# watch_game_2022_revB.net
KiCad netlist of a schematic drawn in EAGLE
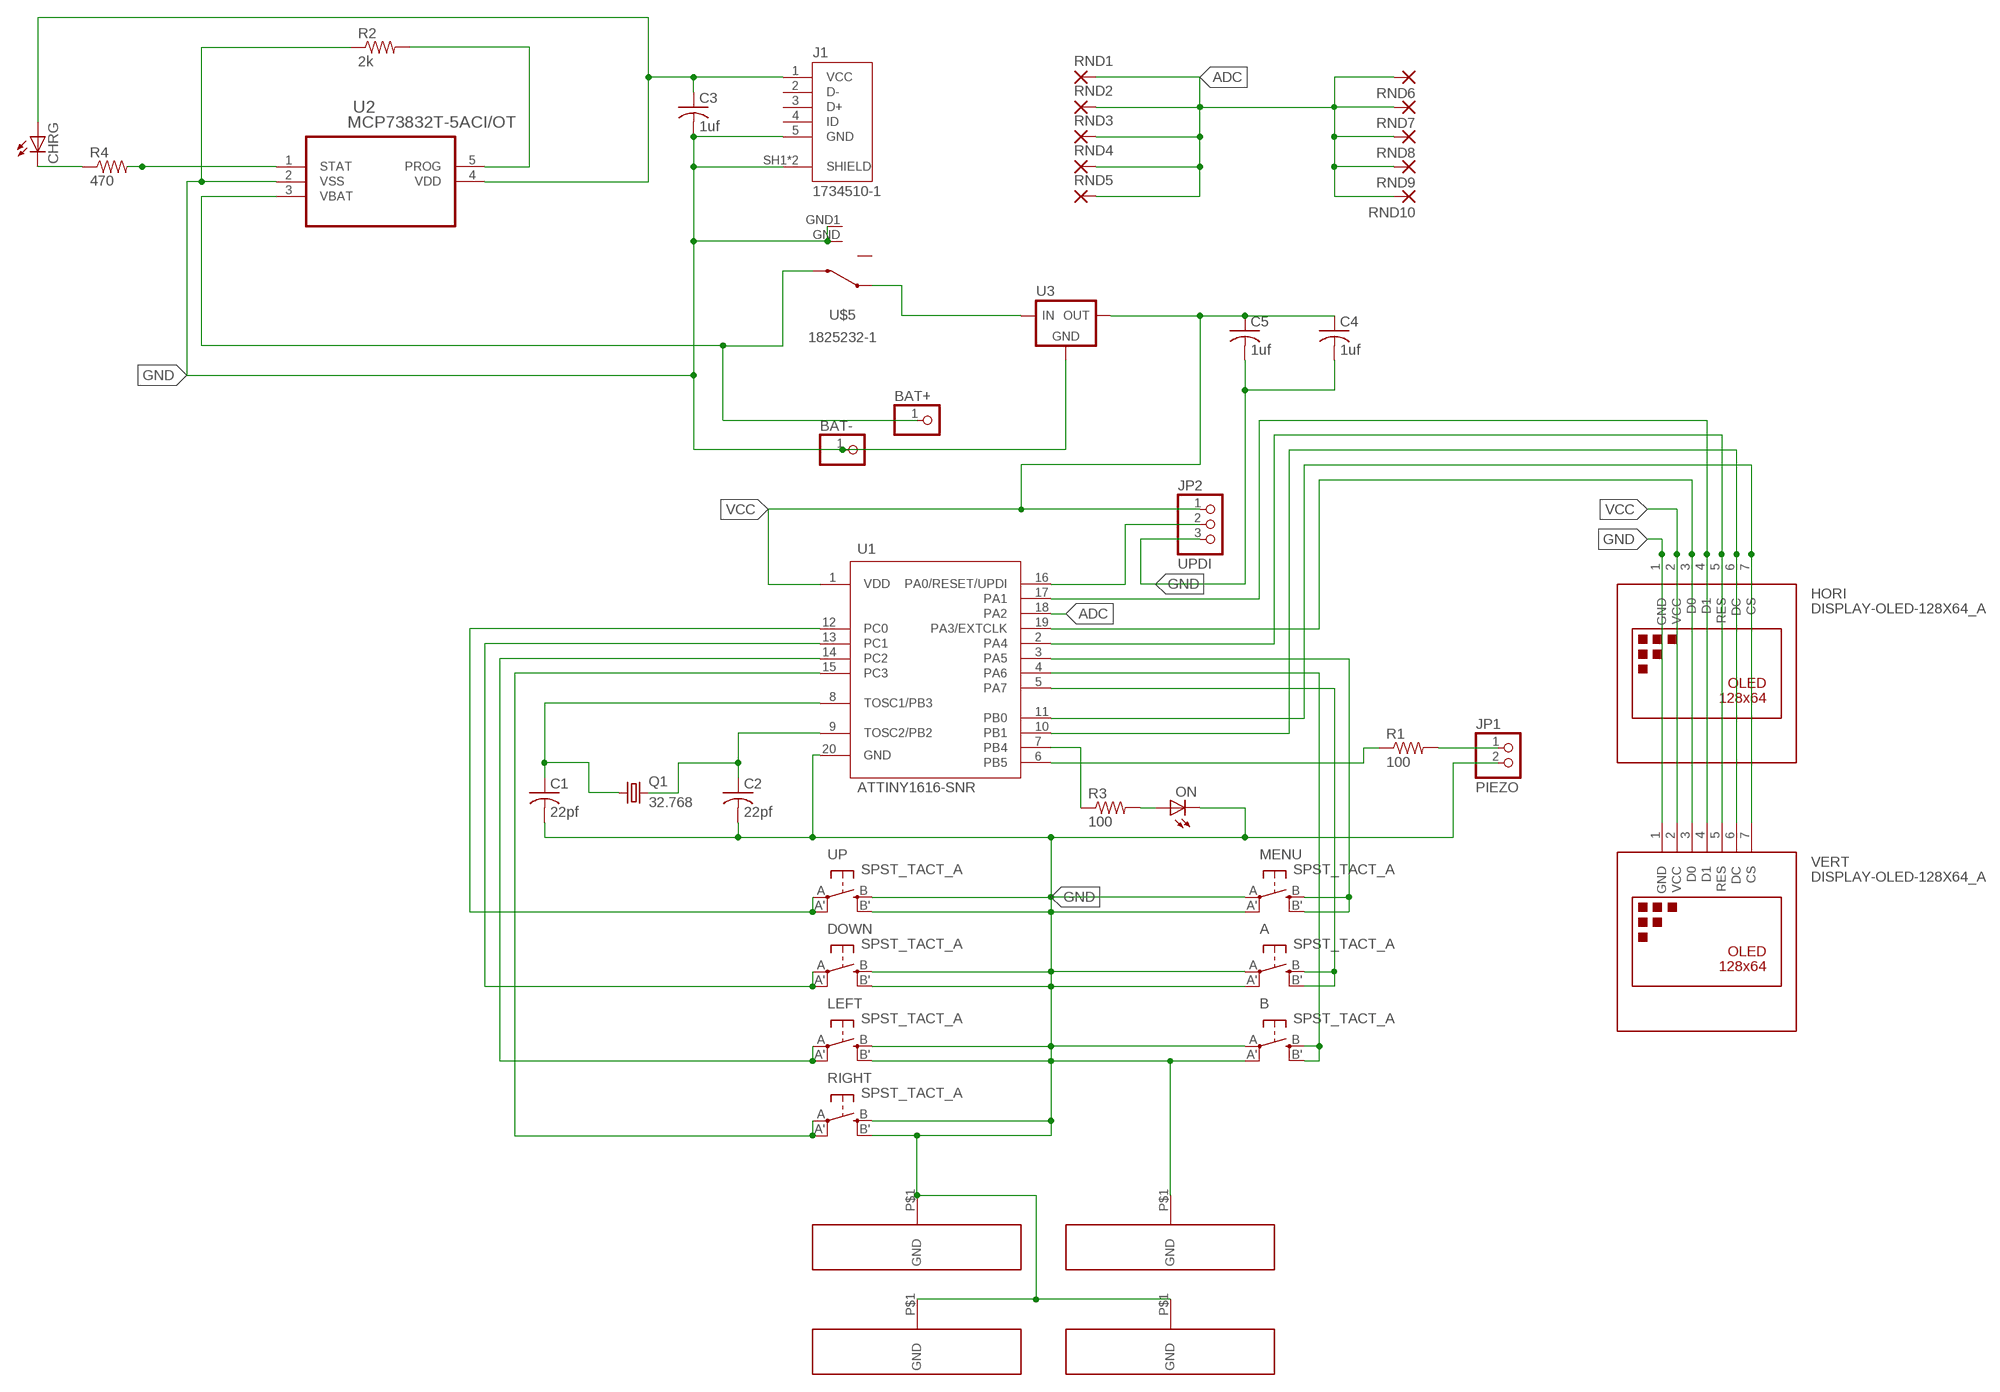
[diagram p0: schematic, sheet 1]

(export (version "E")
  (design (tool "Eeschema 10.0.6"))
  (components
    (comp (ref "A")
      (value "SPST_TACT_A")
      (footprint "eagle-import:EVQ-Q2_A")
      (libsource (lib "eagle-import") (part "SPST_TACT_A"))
    )
    (comp (ref "B")
      (value "SPST_TACT_A")
      (footprint "eagle-import:EVQ-Q2_A")
      (libsource (lib "eagle-import") (part "SPST_TACT_A"))
    )
    (comp (ref "BAT+")
      (value "PINHD-1X1")
      (footprint "eagle-import:1X01")
      (libsource (lib "eagle-import") (part "PINHD-1X1"))
    )
    (comp (ref "BAT-")
      (value "PINHD-1X1")
      (footprint "eagle-import:1X01")
      (libsource (lib "eagle-import") (part "PINHD-1X1"))
    )
    (comp (ref "C1")
      (value "22pf")
      (footprint "eagle-import:C0805")
      (libsource (lib "eagle-import") (part "C-USC0805"))
    )
    (comp (ref "C2")
      (value "22pf")
      (footprint "eagle-import:C0805")
      (libsource (lib "eagle-import") (part "C-USC0805"))
    )
    (comp (ref "C3")
      (value "1uf")
      (footprint "eagle-import:C0805")
      (libsource (lib "eagle-import") (part "rcl_334_C-USC0805"))
    )
    (comp (ref "C4")
      (value "1uf")
      (footprint "eagle-import:C0805")
      (libsource (lib "eagle-import") (part "rcl_334_C-USC0805"))
    )
    (comp (ref "C5")
      (value "1uf")
      (footprint "eagle-import:C0805")
      (libsource (lib "eagle-import") (part "rcl_334_C-USC0805"))
    )
    (comp (ref "CHRG")
      (value "LED3MM")
      (footprint "eagle-import:LED3MM")
      (libsource (lib "eagle-import") (part "LED3MM"))
    )
    (comp (ref "DOWN")
      (value "SPST_TACT_A")
      (footprint "eagle-import:EVQ-Q2_A")
      (libsource (lib "eagle-import") (part "SPST_TACT_A"))
    )
    (comp (ref "HORI")
      (value "DISPLAY-OLED-128X64_A")
      (footprint "eagle-import:DISPLAY-OLED-128X64_A")
      (libsource (lib "eagle-import") (part "DISPLAY-OLED-128X64_A"))
    )
    (comp (ref "J1")
      (value "1734510-1")
      (footprint "eagle-import:TE_1734510-1")
      (fields (field (name "MF") "TE Connectivity"))
      (libsource (lib "eagle-import") (part "1734510-1"))
    )
    (comp (ref "JP1")
      (value "PIEZO")
      (footprint "eagle-import:1X02")
      (libsource (lib "eagle-import") (part "PINHD-1X2"))
    )
    (comp (ref "JP2")
      (value "UPDI")
      (footprint "eagle-import:1X03")
      (libsource (lib "eagle-import") (part "PINHD-1X3"))
    )
    (comp (ref "LEFT")
      (value "SPST_TACT_A")
      (footprint "eagle-import:EVQ-Q2_A")
      (libsource (lib "eagle-import") (part "SPST_TACT_A"))
    )
    (comp (ref "MENU")
      (value "SPST_TACT_A")
      (footprint "eagle-import:EVQ-Q2_A")
      (libsource (lib "eagle-import") (part "SPST_TACT_A"))
    )
    (comp (ref "ON")
      (value "LED5MM")
      (footprint "eagle-import:LED5MM")
      (libsource (lib "eagle-import") (part "led_259_LED5MM"))
    )
    (comp (ref "Q1")
      (value "32.768")
      (footprint "eagle-import:TC26H")
      (libsource (lib "eagle-import") (part "CRYSTALTC26H"))
    )
    (comp (ref "R1")
      (value "100")
      (footprint "eagle-import:M0805")
      (libsource (lib "eagle-import") (part "R-US_M0805"))
    )
    (comp (ref "R2")
      (value "2k")
      (footprint "eagle-import:M0805")
      (libsource (lib "eagle-import") (part "R-US_M0805"))
    )
    (comp (ref "R3")
      (value "100")
      (footprint "eagle-import:M0805")
      (libsource (lib "eagle-import") (part "R-US_M0805"))
    )
    (comp (ref "R4")
      (value "470")
      (footprint "eagle-import:M0805")
      (libsource (lib "eagle-import") (part "R-US_M0805"))
    )
    (comp (ref "RIGHT")
      (value "SPST_TACT_A")
      (footprint "eagle-import:EVQ-Q2_A")
      (libsource (lib "eagle-import") (part "SPST_TACT_A"))
    )
    (comp (ref "RND1")
      (value "SMD5")
      (footprint "eagle-import:SMD2,54-5,08")
      (libsource (lib "eagle-import") (part "SMD5"))
    )
    (comp (ref "RND2")
      (value "SMD5")
      (footprint "eagle-import:SMD2,54-5,08")
      (libsource (lib "eagle-import") (part "SMD5"))
    )
    (comp (ref "RND3")
      (value "SMD5")
      (footprint "eagle-import:SMD2,54-5,08")
      (libsource (lib "eagle-import") (part "SMD5"))
    )
    (comp (ref "RND4")
      (value "SMD5")
      (footprint "eagle-import:SMD2,54-5,08")
      (libsource (lib "eagle-import") (part "SMD5"))
    )
    (comp (ref "RND5")
      (value "SMD5")
      (footprint "eagle-import:SMD2,54-5,08")
      (libsource (lib "eagle-import") (part "SMD5"))
    )
    (comp (ref "RND6")
      (value "SMD5")
      (footprint "eagle-import:SMD2,54-5,08")
      (libsource (lib "eagle-import") (part "SMD5"))
    )
    (comp (ref "RND7")
      (value "SMD5")
      (footprint "eagle-import:SMD2,54-5,08")
      (libsource (lib "eagle-import") (part "SMD5"))
    )
    (comp (ref "RND8")
      (value "SMD5")
      (footprint "eagle-import:SMD2,54-5,08")
      (libsource (lib "eagle-import") (part "SMD5"))
    )
    (comp (ref "RND9")
      (value "SMD5")
      (footprint "eagle-import:SMD2,54-5,08")
      (libsource (lib "eagle-import") (part "SMD5"))
    )
    (comp (ref "RND10")
      (value "SMD5")
      (footprint "eagle-import:SMD2,54-5,08")
      (libsource (lib "eagle-import") (part "SMD5"))
    )
    (comp (ref "U$5")
      (value "1825232-1")
      (footprint "eagle-import:1825232-1")
      (fields (field (name "MF") "TE Connectivity"))
      (libsource (lib "eagle-import") (part "1825232-1"))
    )
    (comp (ref "U$6")
      (value "GND_STRIP_600MIL")
      (footprint "eagle-import:GND_PADS_2")
      (libsource (lib "eagle-import") (part "GND_STRIP_600MIL"))
    )
    (comp (ref "U$7")
      (value "GND_STRIP_600MIL")
      (footprint "eagle-import:GND_PADS_2")
      (libsource (lib "eagle-import") (part "GND_STRIP_600MIL"))
    )
    (comp (ref "U$8")
      (value "GND_STRIP_600MIL")
      (footprint "eagle-import:GND_PADS_2")
      (libsource (lib "eagle-import") (part "GND_STRIP_600MIL"))
    )
    (comp (ref "U$9")
      (value "GND_STRIP_600MIL")
      (footprint "eagle-import:GND_PADS_2")
      (libsource (lib "eagle-import") (part "GND_STRIP_600MIL"))
    )
    (comp (ref "U1")
      (value "ATTINY1616-SNR")
      (footprint "eagle-import:SOIC127P1032X265-20N")
      (fields (field (name "MF") "Microchip"))
      (libsource (lib "eagle-import") (part "ATTINY1616-SNR"))
    )
    (comp (ref "U2")
      (value "MCP73832T-5ACI/OT")
      (footprint "eagle-import:SOT95P300X145-5N")
      (fields (field (name "MF") "Microchip"))
      (libsource (lib "eagle-import") (part "MCP73832T-5ACI/OT"))
    )
    (comp (ref "U3")
      (value "NCP5501DT33RKG")
      (footprint "eagle-import:DPAK")
      (libsource (lib "eagle-import") (part "NCP5501DT33RKG"))
    )
    (comp (ref "UP")
      (value "SPST_TACT_A")
      (footprint "eagle-import:EVQ-Q2_A")
      (libsource (lib "eagle-import") (part "SPST_TACT_A"))
    )
    (comp (ref "VERT")
      (value "DISPLAY-OLED-128X64_A")
      (footprint "eagle-import:DISPLAY-OLED-128X64_A")
      (libsource (lib "eagle-import") (part "DISPLAY-OLED-128X64_A"))
    )
  )
  (nets
    (net (code "1") (name "ADC") (class "Default")
      (node (ref "RND1") (pin "1") (pinfunction "P_1") (pintype "passive"))
      (node (ref "RND10") (pin "1") (pinfunction "P_1") (pintype "passive"))
      (node (ref "RND2") (pin "1") (pinfunction "P_1") (pintype "passive"))
      (node (ref "RND3") (pin "1") (pinfunction "P_1") (pintype "passive"))
      (node (ref "RND4") (pin "1") (pinfunction "P_1") (pintype "passive"))
      (node (ref "RND5") (pin "1") (pinfunction "P_1") (pintype "passive"))
      (node (ref "RND6") (pin "1") (pinfunction "P_1") (pintype "passive"))
      (node (ref "RND7") (pin "1") (pinfunction "P_1") (pintype "passive"))
      (node (ref "RND8") (pin "1") (pinfunction "P_1") (pintype "passive"))
      (node (ref "RND9") (pin "1") (pinfunction "P_1") (pintype "passive"))
      (node (ref "U1") (pin "18") (pinfunction "PA2_18") (pintype "bidirectional"))
    )
    (net (code "2") (name "GND") (class "Default")
      (node (ref "A") (pin "A") (pinfunction "P_A") (pintype "passive"))
      (node (ref "A") (pin "A'") (pinfunction "P1_A'") (pintype "passive"))
      (node (ref "B") (pin "A") (pinfunction "P_A") (pintype "passive"))
      (node (ref "B") (pin "A'") (pinfunction "P1_A'") (pintype "passive"))
      (node (ref "BAT-") (pin "1") (pinfunction "1_1") (pintype "passive"))
      (node (ref "C1") (pin "2") (pinfunction "2_2") (pintype "passive"))
      (node (ref "C2") (pin "2") (pinfunction "2_2") (pintype "passive"))
      (node (ref "C3") (pin "2") (pinfunction "2_2") (pintype "passive"))
      (node (ref "C4") (pin "2") (pinfunction "2_2") (pintype "passive"))
      (node (ref "C5") (pin "2") (pinfunction "2_2") (pintype "passive"))
      (node (ref "DOWN") (pin "B") (pinfunction "S_B") (pintype "passive"))
      (node (ref "DOWN") (pin "B'") (pinfunction "S1_B'") (pintype "passive"))
      (node (ref "HORI") (pin "1") (pinfunction "GND_1") (pintype "power_in"))
      (node (ref "J1") (pin "5") (pinfunction "GND_5") (pintype "passive"))
      (node (ref "J1") (pin "SH1") (pinfunction "SHIELD_SH1") (pintype "passive"))
      (node (ref "J1") (pin "SH2") (pinfunction "SHIELD_SH2") (pintype "passive"))
      (node (ref "JP1") (pin "2") (pinfunction "2_2") (pintype "passive"))
      (node (ref "JP2") (pin "3") (pinfunction "3_3") (pintype "passive"))
      (node (ref "LEFT") (pin "B") (pinfunction "S_B") (pintype "passive"))
      (node (ref "LEFT") (pin "B'") (pinfunction "S1_B'") (pintype "passive"))
      (node (ref "MENU") (pin "A") (pinfunction "P_A") (pintype "passive"))
      (node (ref "MENU") (pin "A'") (pinfunction "P1_A'") (pintype "passive"))
      (node (ref "ON") (pin "K") (pinfunction "C_K") (pintype "passive"))
      (node (ref "R2") (pin "1") (pinfunction "1_1") (pintype "passive"))
      (node (ref "RIGHT") (pin "B") (pinfunction "S_B") (pintype "passive"))
      (node (ref "RIGHT") (pin "B'") (pinfunction "S1_B'") (pintype "passive"))
      (node (ref "U$5") (pin "GND") (pinfunction "GND_GND") (pintype "passive"))
      (node (ref "U$5") (pin "GND1") (pinfunction "GND1_GND1") (pintype "passive"))
      (node (ref "U$6") (pin "P$1") (pinfunction "GND_P$1") (pintype "bidirectional"))
      (node (ref "U$7") (pin "P$1") (pinfunction "GND_P$1") (pintype "bidirectional"))
      (node (ref "U$8") (pin "P$1") (pinfunction "GND_P$1") (pintype "bidirectional"))
      (node (ref "U$9") (pin "P$1") (pinfunction "GND_P$1") (pintype "bidirectional"))
      (node (ref "U1") (pin "20") (pinfunction "GND_20") (pintype "power_in"))
      (node (ref "U2") (pin "2") (pinfunction "VSS_2") (pintype "passive"))
      (node (ref "U3") (pin "4") (pinfunction "GND_4") (pintype "power_in"))
      (node (ref "UP") (pin "B") (pinfunction "S_B") (pintype "passive"))
      (node (ref "UP") (pin "B'") (pinfunction "S1_B'") (pintype "passive"))
      (node (ref "VERT") (pin "1") (pinfunction "GND_1") (pintype "power_in"))
    )
    (net (code "3") (name "Net-(A-S)") (class "Default")
      (node (ref "A") (pin "B") (pinfunction "S_B") (pintype "passive"))
      (node (ref "A") (pin "B'") (pinfunction "S1_B'") (pintype "passive"))
      (node (ref "U1") (pin "5") (pinfunction "PA7_5") (pintype "bidirectional"))
    )
    (net (code "4") (name "Net-(B-S)") (class "Default")
      (node (ref "B") (pin "B") (pinfunction "S_B") (pintype "passive"))
      (node (ref "B") (pin "B'") (pinfunction "S1_B'") (pintype "passive"))
      (node (ref "U1") (pin "4") (pinfunction "PA6_4") (pintype "bidirectional"))
    )
    (net (code "5") (name "Net-(CHRG-C)") (class "Default")
      (node (ref "CHRG") (pin "K") (pinfunction "C_K") (pintype "passive"))
      (node (ref "R4") (pin "1") (pinfunction "1_1") (pintype "passive"))
    )
    (net (code "6") (name "Net-(DOWN-P)") (class "Default")
      (node (ref "DOWN") (pin "A") (pinfunction "P_A") (pintype "passive"))
      (node (ref "DOWN") (pin "A'") (pinfunction "P1_A'") (pintype "passive"))
      (node (ref "U1") (pin "13") (pinfunction "PC1_13") (pintype "bidirectional"))
    )
    (net (code "7") (name "Net-(HORI-CS)") (class "Default")
      (node (ref "HORI") (pin "7") (pinfunction "CS_7") (pintype "bidirectional"))
      (node (ref "U1") (pin "11") (pinfunction "PB0_11") (pintype "bidirectional"))
      (node (ref "VERT") (pin "7") (pinfunction "CS_7") (pintype "bidirectional"))
    )
    (net (code "8") (name "Net-(HORI-D0)") (class "Default")
      (node (ref "HORI") (pin "3") (pinfunction "D0_3") (pintype "bidirectional"))
      (node (ref "U1") (pin "19") (pinfunction "PA3/EXTCLK_19") (pintype "bidirectional"))
      (node (ref "VERT") (pin "3") (pinfunction "D0_3") (pintype "bidirectional"))
    )
    (net (code "9") (name "Net-(HORI-D1)") (class "Default")
      (node (ref "HORI") (pin "4") (pinfunction "D1_4") (pintype "bidirectional"))
      (node (ref "U1") (pin "17") (pinfunction "PA1_17") (pintype "bidirectional"))
      (node (ref "VERT") (pin "4") (pinfunction "D1_4") (pintype "bidirectional"))
    )
    (net (code "10") (name "Net-(HORI-DC)") (class "Default")
      (node (ref "HORI") (pin "6") (pinfunction "DC_6") (pintype "bidirectional"))
      (node (ref "U1") (pin "10") (pinfunction "PB1_10") (pintype "bidirectional"))
      (node (ref "VERT") (pin "6") (pinfunction "DC_6") (pintype "bidirectional"))
    )
    (net (code "11") (name "Net-(HORI-RES)") (class "Default")
      (node (ref "HORI") (pin "5") (pinfunction "RES_5") (pintype "bidirectional"))
      (node (ref "U1") (pin "2") (pinfunction "PA4_2") (pintype "bidirectional"))
      (node (ref "VERT") (pin "5") (pinfunction "RES_5") (pintype "bidirectional"))
    )
    (net (code "12") (name "Net-(J1-VCC)") (class "Default")
      (node (ref "C3") (pin "1") (pinfunction "1_1") (pintype "passive"))
      (node (ref "CHRG") (pin "A") (pinfunction "A_A") (pintype "passive"))
      (node (ref "J1") (pin "1") (pinfunction "VCC_1") (pintype "passive"))
      (node (ref "U2") (pin "4") (pinfunction "VDD_4") (pintype "power_in"))
    )
    (net (code "13") (name "Net-(JP1-Pad1)") (class "Default")
      (node (ref "JP1") (pin "1") (pinfunction "1_1") (pintype "passive"))
      (node (ref "R1") (pin "2") (pinfunction "2_2") (pintype "passive"))
    )
    (net (code "14") (name "Net-(LEFT-P)") (class "Default")
      (node (ref "LEFT") (pin "A") (pinfunction "P_A") (pintype "passive"))
      (node (ref "LEFT") (pin "A'") (pinfunction "P1_A'") (pintype "passive"))
      (node (ref "U1") (pin "14") (pinfunction "PC2_14") (pintype "bidirectional"))
    )
    (net (code "15") (name "Net-(MENU-S)") (class "Default")
      (node (ref "MENU") (pin "B") (pinfunction "S_B") (pintype "passive"))
      (node (ref "MENU") (pin "B'") (pinfunction "S1_B'") (pintype "passive"))
      (node (ref "U1") (pin "3") (pinfunction "PA5_3") (pintype "bidirectional"))
    )
    (net (code "16") (name "Net-(ON-PadA)") (class "Default")
      (node (ref "ON") (pin "A") (pinfunction "A_A") (pintype "passive"))
      (node (ref "R3") (pin "2") (pinfunction "2_2") (pintype "passive"))
    )
    (net (code "17") (name "Net-(RIGHT-P)") (class "Default")
      (node (ref "RIGHT") (pin "A") (pinfunction "P_A") (pintype "passive"))
      (node (ref "RIGHT") (pin "A'") (pinfunction "P1_A'") (pintype "passive"))
      (node (ref "U1") (pin "15") (pinfunction "PC3_15") (pintype "bidirectional"))
    )
    (net (code "18") (name "Net-(U1-PA0{slash}RESET{slash}UPDI)") (class "Default")
      (node (ref "JP2") (pin "2") (pinfunction "2_2") (pintype "passive"))
      (node (ref "U1") (pin "16") (pinfunction "PA0/RESET/UPDI_16") (pintype "bidirectional"))
    )
    (net (code "19") (name "Net-(U1-PB4)") (class "Default")
      (node (ref "R3") (pin "1") (pinfunction "1_1") (pintype "passive"))
      (node (ref "U1") (pin "7") (pinfunction "PB4_7") (pintype "bidirectional"))
    )
    (net (code "20") (name "Net-(U1-PB5)") (class "Default")
      (node (ref "R1") (pin "1") (pinfunction "1_1") (pintype "passive"))
      (node (ref "U1") (pin "6") (pinfunction "PB5_6") (pintype "bidirectional"))
    )
    (net (code "21") (name "Net-(U1-PC0)") (class "Default")
      (node (ref "U1") (pin "12") (pinfunction "PC0_12") (pintype "bidirectional"))
      (node (ref "UP") (pin "A") (pinfunction "P_A") (pintype "passive"))
      (node (ref "UP") (pin "A'") (pinfunction "P1_A'") (pintype "passive"))
    )
    (net (code "22") (name "Net-(U1-TOSC1{slash}PB3)") (class "Default")
      (node (ref "C1") (pin "1") (pinfunction "1_1") (pintype "passive"))
      (node (ref "Q1") (pin "1") (pinfunction "1_1") (pintype "passive"))
      (node (ref "U1") (pin "8") (pinfunction "TOSC1/PB3_8") (pintype "bidirectional"))
    )
    (net (code "23") (name "Net-(U1-TOSC2{slash}PB2)") (class "Default")
      (node (ref "C2") (pin "1") (pinfunction "1_1") (pintype "passive"))
      (node (ref "Q1") (pin "2") (pinfunction "2_2") (pintype "passive"))
      (node (ref "U1") (pin "9") (pinfunction "TOSC2/PB2_9") (pintype "bidirectional"))
    )
    (net (code "24") (name "Net-(U2-PROG)") (class "Default")
      (node (ref "R2") (pin "2") (pinfunction "2_2") (pintype "passive"))
      (node (ref "U2") (pin "5") (pinfunction "PROG_5") (pintype "input"))
    )
    (net (code "25") (name "Net-(U2-STAT)") (class "Default")
      (node (ref "R4") (pin "2") (pinfunction "2_2") (pintype "passive"))
      (node (ref "U2") (pin "1") (pinfunction "STAT_1") (pintype "input"))
    )
    (net (code "26") (name "Net-(U2-VBAT)") (class "Default")
      (node (ref "BAT+") (pin "1") (pinfunction "1_1") (pintype "passive"))
      (node (ref "U$5") (pin "2") (pinfunction "2_2") (pintype "passive"))
      (node (ref "U2") (pin "3") (pinfunction "VBAT_3") (pintype "input"))
    )
    (net (code "27") (name "Net-(U3-VIN)") (class "Default")
      (node (ref "U$5") (pin "3") (pinfunction "3_3") (pintype "passive"))
      (node (ref "U3") (pin "1") (pinfunction "VIN_1") (pintype "power_in"))
    )
    (net (code "28") (name "VCC") (class "Default")
      (node (ref "C4") (pin "1") (pinfunction "1_1") (pintype "passive"))
      (node (ref "C5") (pin "1") (pinfunction "1_1") (pintype "passive"))
      (node (ref "HORI") (pin "2") (pinfunction "VCC_2") (pintype "power_in"))
      (node (ref "JP2") (pin "1") (pinfunction "1_1") (pintype "passive"))
      (node (ref "U1") (pin "1") (pinfunction "VDD_1") (pintype "power_in"))
      (node (ref "U3") (pin "3") (pinfunction "VOUT_3") (pintype "power_in"))
      (node (ref "VERT") (pin "2") (pinfunction "VCC_2") (pintype "power_in"))
    )
    (net (code "29") (name "unconnected-(J1-D+-Pad3)") (class "Default")
      (node (ref "J1") (pin "3") (pinfunction "D+_3") (pintype "passive"))
    )
    (net (code "30") (name "unconnected-(J1-D--Pad2)") (class "Default")
      (node (ref "J1") (pin "2") (pinfunction "D-_2") (pintype "passive"))
    )
    (net (code "31") (name "unconnected-(J1-ID-Pad4)") (class "Default")
      (node (ref "J1") (pin "4") (pinfunction "ID_4") (pintype "passive"))
    )
    (net (code "32") (name "unconnected-(U$5-Pad1)") (class "Default")
      (node (ref "U$5") (pin "1") (pinfunction "1_1") (pintype "passive"))
    )
  )
)
